# IN.net
KiCad netlist of a schematic drawn in Altium Designer
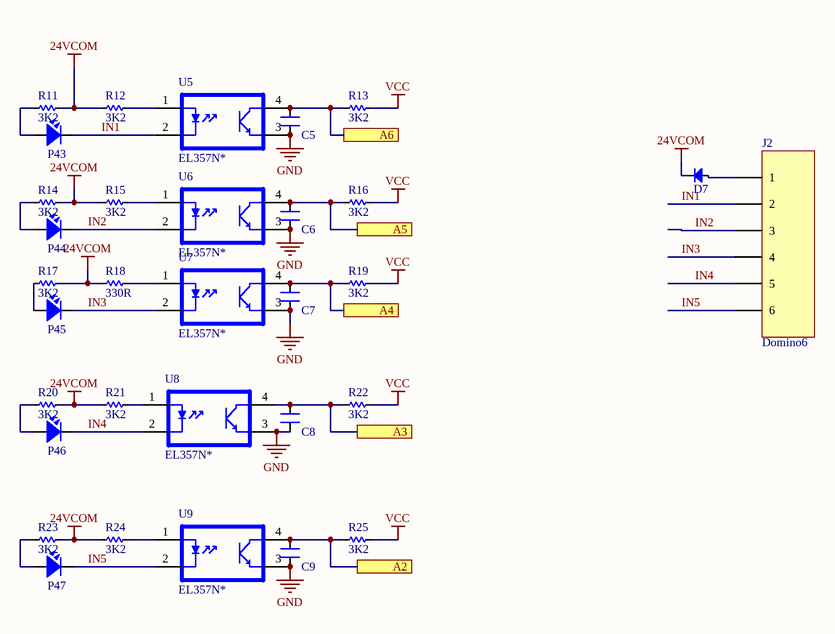
[diagram p0: IN.SchDoc]

(export (version "E")
  (design (tool "Eeschema 10.0.6"))
  (components
    (comp (ref "C5") (value "100nF") (footprint "CN-SMD-0805") (libsource (lib "nhan") (part "CN")))
    (comp (ref "C6") (value "100nF") (footprint "CN-SMD-0805") (libsource (lib "nhan") (part "CN")))
    (comp (ref "C7") (value "100nF") (footprint "CN-SMD-0805") (libsource (lib "nhan") (part "CN")))
    (comp (ref "C8") (value "100nF") (footprint "CN-SMD-0805") (libsource (lib "nhan") (part "CN")))
    (comp (ref "C9") (value "100nF") (footprint "CN-SMD-0805") (libsource (lib "nhan") (part "CN")))
    (comp (ref "D7")
      (value "Diode")
      (footprint "DIO-SMD-123")
      (description "Default Diode")
      (fields (field (name "PUBLISHER") "Altium Limited"))
      (libsource (lib "nhan") (part "Diode"))
    )
    (comp (ref "J2")
      (value "Domino6")
      (footprint "KF6-5.08T")
      (fields
        (field (name "MANUFACTURER") "Würth Elektronik eiSos GmbH")
        (field (name "PARTNO") "691133710006")
        (field (name "CREATED BY") "Baojun Chen")
      )
      (libsource (lib "nhan") (part "Domino6"))
    )
    (comp (ref "P43")
      (value "LED")
      (footprint "LED-0805-Green")
      (libsource (lib "BanLinhKien") (part "LED SMD"))
    )
    (comp (ref "P44")
      (value "LED")
      (footprint "LED-0805-Green")
      (libsource (lib "BanLinhKien") (part "LED SMD"))
    )
    (comp (ref "P45")
      (value "LED")
      (footprint "LED-0805-Green")
      (libsource (lib "BanLinhKien") (part "LED SMD"))
    )
    (comp (ref "P46")
      (value "LED")
      (footprint "LED-0805-Green")
      (libsource (lib "BanLinhKien") (part "LED SMD"))
    )
    (comp (ref "P47")
      (value "LED")
      (footprint "LED-0805-Green")
      (libsource (lib "BanLinhKien") (part "LED SMD"))
    )
    (comp (ref "R11") (value "3K2") (footprint "RES-SMD-0805") (libsource (lib "nhan") (part "R")))
    (comp (ref "R12") (value "3K2") (footprint "RES-SMD-0805") (libsource (lib "nhan") (part "R")))
    (comp (ref "R13") (value "3K2") (footprint "RES-SMD-0805") (libsource (lib "nhan") (part "R")))
    (comp (ref "R14") (value "3K2") (footprint "RES-SMD-0805") (libsource (lib "nhan") (part "R")))
    (comp (ref "R15") (value "3K2") (footprint "RES-SMD-0805") (libsource (lib "nhan") (part "R")))
    (comp (ref "R16") (value "3K2") (footprint "RES-SMD-0805") (libsource (lib "nhan") (part "R")))
    (comp (ref "R17") (value "3K2") (footprint "RES-SMD-0805") (libsource (lib "nhan") (part "R")))
    (comp (ref "R18") (value "330R") (footprint "RES-SMD-0805") (libsource (lib "nhan") (part "R")))
    (comp (ref "R19") (value "3K2") (footprint "RES-SMD-0805") (libsource (lib "nhan") (part "R")))
    (comp (ref "R20") (value "3K2") (footprint "RES-SMD-0805") (libsource (lib "nhan") (part "R")))
    (comp (ref "R21") (value "3K2") (footprint "RES-SMD-0805") (libsource (lib "nhan") (part "R")))
    (comp (ref "R22") (value "3K2") (footprint "RES-SMD-0805") (libsource (lib "nhan") (part "R")))
    (comp (ref "R23") (value "3K2") (footprint "RES-SMD-0805") (libsource (lib "nhan") (part "R")))
    (comp (ref "R24") (value "3K2") (footprint "RES-SMD-0805") (libsource (lib "nhan") (part "R")))
    (comp (ref "R25") (value "3K2") (footprint "RES-SMD-0805") (libsource (lib "nhan") (part "R")))
    (comp (ref "U5")
      (value "EL357N*")
      (footprint "SOP4N")
      (description "Optoisolator Transistor Output 3750Vrms 1 Channel 4-SOP _2.54mm_")
      (fields (field (name "MP") "EL357N_A__TA_-G") (field (name "MF") "Everlight Electronics"))
      (libsource (lib "nhan") (part "EL357N(A)(TA)-G"))
    )
    (comp (ref "U6")
      (value "EL357N*")
      (footprint "SOP4N")
      (description "Optoisolator Transistor Output 3750Vrms 1 Channel 4-SOP _2.54mm_")
      (fields (field (name "MP") "EL357N_A__TA_-G") (field (name "MF") "Everlight Electronics"))
      (libsource (lib "nhan") (part "EL357N(A)(TA)-G"))
    )
    (comp (ref "U7")
      (value "EL357N*")
      (footprint "SOP4N")
      (description "Optoisolator Transistor Output 3750Vrms 1 Channel 4-SOP _2.54mm_")
      (fields (field (name "MP") "EL357N_A__TA_-G") (field (name "MF") "Everlight Electronics"))
      (libsource (lib "nhan") (part "EL357N(A)(TA)-G"))
    )
    (comp (ref "U8")
      (value "EL357N*")
      (footprint "SOP4N")
      (description "Optoisolator Transistor Output 3750Vrms 1 Channel 4-SOP _2.54mm_")
      (fields (field (name "MP") "EL357N_A__TA_-G") (field (name "MF") "Everlight Electronics"))
      (libsource (lib "nhan") (part "EL357N(A)(TA)-G"))
    )
    (comp (ref "U9")
      (value "EL357N*")
      (footprint "SOP4N")
      (description "Optoisolator Transistor Output 3750Vrms 1 Channel 4-SOP _2.54mm_")
      (fields (field (name "MP") "EL357N_A__TA_-G") (field (name "MF") "Everlight Electronics"))
      (libsource (lib "nhan") (part "EL357N(A)(TA)-G"))
    )
  )
  (nets
    (net (code "1") (name "/A2") (class "Default")
      (node (ref "C9") (pin "1") (pinfunction "1_1") (pintype "passive"))
      (node (ref "R25") (pin "1") (pinfunction "1_1") (pintype "passive"))
      (node (ref "U9") (pin "4") (pinfunction "C_4") (pintype "passive"))
    )
    (net (code "2") (name "/A3") (class "Default")
      (node (ref "C8") (pin "1") (pinfunction "1_1") (pintype "passive"))
      (node (ref "R22") (pin "1") (pinfunction "1_1") (pintype "passive"))
      (node (ref "U8") (pin "4") (pinfunction "C_4") (pintype "passive"))
    )
    (net (code "3") (name "/A4") (class "Default")
      (node (ref "C7") (pin "1") (pinfunction "1_1") (pintype "passive"))
      (node (ref "R19") (pin "1") (pinfunction "1_1") (pintype "passive"))
      (node (ref "U7") (pin "4") (pinfunction "C_4") (pintype "passive"))
    )
    (net (code "4") (name "/A5") (class "Default")
      (node (ref "C6") (pin "1") (pinfunction "1_1") (pintype "passive"))
      (node (ref "R16") (pin "1") (pinfunction "1_1") (pintype "passive"))
      (node (ref "U6") (pin "4") (pinfunction "C_4") (pintype "passive"))
    )
    (net (code "5") (name "/A6") (class "Default")
      (node (ref "C5") (pin "1") (pinfunction "1_1") (pintype "passive"))
      (node (ref "R13") (pin "1") (pinfunction "1_1") (pintype "passive"))
      (node (ref "U5") (pin "4") (pinfunction "C_4") (pintype "passive"))
    )
    (net (code "6") (name "/IN1") (class "Default")
      (node (ref "J2") (pin "2") (pinfunction "2_2") (pintype "passive"))
      (node (ref "P43") (pin "2") (pinfunction "2_2") (pintype "passive"))
      (node (ref "U5") (pin "2") (pinfunction "K_2") (pintype "passive"))
    )
    (net (code "7") (name "/IN2") (class "Default")
      (node (ref "J2") (pin "3") (pinfunction "3_3") (pintype "passive"))
      (node (ref "P44") (pin "2") (pinfunction "2_2") (pintype "passive"))
      (node (ref "U6") (pin "2") (pinfunction "K_2") (pintype "passive"))
    )
    (net (code "8") (name "/IN3") (class "Default")
      (node (ref "J2") (pin "4") (pinfunction "4_4") (pintype "passive"))
      (node (ref "P45") (pin "2") (pinfunction "2_2") (pintype "passive"))
      (node (ref "U7") (pin "2") (pinfunction "K_2") (pintype "passive"))
    )
    (net (code "9") (name "/IN4") (class "Default")
      (node (ref "J2") (pin "5") (pinfunction "5_5") (pintype "passive"))
      (node (ref "P46") (pin "2") (pinfunction "2_2") (pintype "passive"))
      (node (ref "U8") (pin "2") (pinfunction "K_2") (pintype "passive"))
    )
    (net (code "10") (name "/IN5") (class "Default")
      (node (ref "J2") (pin "6") (pinfunction "6_6") (pintype "passive"))
      (node (ref "P47") (pin "2") (pinfunction "2_2") (pintype "passive"))
      (node (ref "U9") (pin "2") (pinfunction "K_2") (pintype "passive"))
    )
    (net (code "11") (name "24VCOM") (class "Default")
      (node (ref "D7") (pin "2") (pinfunction "K_2") (pintype "passive"))
      (node (ref "R11") (pin "1") (pinfunction "1_1") (pintype "passive"))
      (node (ref "R12") (pin "1") (pinfunction "1_1") (pintype "passive"))
      (node (ref "R14") (pin "1") (pinfunction "1_1") (pintype "passive"))
      (node (ref "R15") (pin "1") (pinfunction "1_1") (pintype "passive"))
      (node (ref "R17") (pin "1") (pinfunction "1_1") (pintype "passive"))
      (node (ref "R18") (pin "1") (pinfunction "1_1") (pintype "passive"))
      (node (ref "R20") (pin "1") (pinfunction "1_1") (pintype "passive"))
      (node (ref "R21") (pin "1") (pinfunction "1_1") (pintype "passive"))
      (node (ref "R23") (pin "1") (pinfunction "1_1") (pintype "passive"))
      (node (ref "R24") (pin "1") (pinfunction "1_1") (pintype "passive"))
    )
    (net (code "12") (name "GND") (class "Default")
      (node (ref "C5") (pin "2") (pinfunction "2_2") (pintype "passive"))
      (node (ref "C6") (pin "2") (pinfunction "2_2") (pintype "passive"))
      (node (ref "C7") (pin "2") (pinfunction "2_2") (pintype "passive"))
      (node (ref "C8") (pin "2") (pinfunction "2_2") (pintype "passive"))
      (node (ref "C9") (pin "2") (pinfunction "2_2") (pintype "passive"))
      (node (ref "U5") (pin "3") (pinfunction "E_3") (pintype "passive"))
      (node (ref "U6") (pin "3") (pinfunction "E_3") (pintype "passive"))
      (node (ref "U7") (pin "3") (pinfunction "E_3") (pintype "passive"))
      (node (ref "U8") (pin "3") (pinfunction "E_3") (pintype "passive"))
      (node (ref "U9") (pin "3") (pinfunction "E_3") (pintype "passive"))
    )
    (net (code "13") (name "Net-(D7-A)") (class "Default")
      (node (ref "D7") (pin "1") (pinfunction "A_1") (pintype "passive"))
      (node (ref "J2") (pin "1") (pinfunction "1_1") (pintype "passive"))
    )
    (net (code "14") (name "Net-(P43-Pad1)") (class "Default")
      (node (ref "P43") (pin "1") (pinfunction "1_1") (pintype "passive"))
      (node (ref "R11") (pin "2") (pinfunction "2_2") (pintype "passive"))
    )
    (net (code "15") (name "Net-(P44-Pad1)") (class "Default")
      (node (ref "P44") (pin "1") (pinfunction "1_1") (pintype "passive"))
      (node (ref "R14") (pin "2") (pinfunction "2_2") (pintype "passive"))
    )
    (net (code "16") (name "Net-(P45-Pad1)") (class "Default")
      (node (ref "P45") (pin "1") (pinfunction "1_1") (pintype "passive"))
      (node (ref "R17") (pin "2") (pinfunction "2_2") (pintype "passive"))
    )
    (net (code "17") (name "Net-(P46-Pad1)") (class "Default")
      (node (ref "P46") (pin "1") (pinfunction "1_1") (pintype "passive"))
      (node (ref "R20") (pin "2") (pinfunction "2_2") (pintype "passive"))
    )
    (net (code "18") (name "Net-(P47-Pad1)") (class "Default")
      (node (ref "P47") (pin "1") (pinfunction "1_1") (pintype "passive"))
      (node (ref "R23") (pin "2") (pinfunction "2_2") (pintype "passive"))
    )
    (net (code "19") (name "Net-(U5-A)") (class "Default")
      (node (ref "R12") (pin "2") (pinfunction "2_2") (pintype "passive"))
      (node (ref "U5") (pin "1") (pinfunction "A_1") (pintype "passive"))
    )
    (net (code "20") (name "Net-(U6-A)") (class "Default")
      (node (ref "R15") (pin "2") (pinfunction "2_2") (pintype "passive"))
      (node (ref "U6") (pin "1") (pinfunction "A_1") (pintype "passive"))
    )
    (net (code "21") (name "Net-(U7-A)") (class "Default")
      (node (ref "R18") (pin "2") (pinfunction "2_2") (pintype "passive"))
      (node (ref "U7") (pin "1") (pinfunction "A_1") (pintype "passive"))
    )
    (net (code "22") (name "Net-(U8-A)") (class "Default")
      (node (ref "R21") (pin "2") (pinfunction "2_2") (pintype "passive"))
      (node (ref "U8") (pin "1") (pinfunction "A_1") (pintype "passive"))
    )
    (net (code "23") (name "Net-(U9-A)") (class "Default")
      (node (ref "R24") (pin "2") (pinfunction "2_2") (pintype "passive"))
      (node (ref "U9") (pin "1") (pinfunction "A_1") (pintype "passive"))
    )
    (net (code "24") (name "VCC") (class "Default")
      (node (ref "R13") (pin "2") (pinfunction "2_2") (pintype "passive"))
      (node (ref "R16") (pin "2") (pinfunction "2_2") (pintype "passive"))
      (node (ref "R19") (pin "2") (pinfunction "2_2") (pintype "passive"))
      (node (ref "R22") (pin "2") (pinfunction "2_2") (pintype "passive"))
      (node (ref "R25") (pin "2") (pinfunction "2_2") (pintype "passive"))
    )
  )
)
